# Lamps.net
KiCad netlist of a schematic drawn in Altium Designer
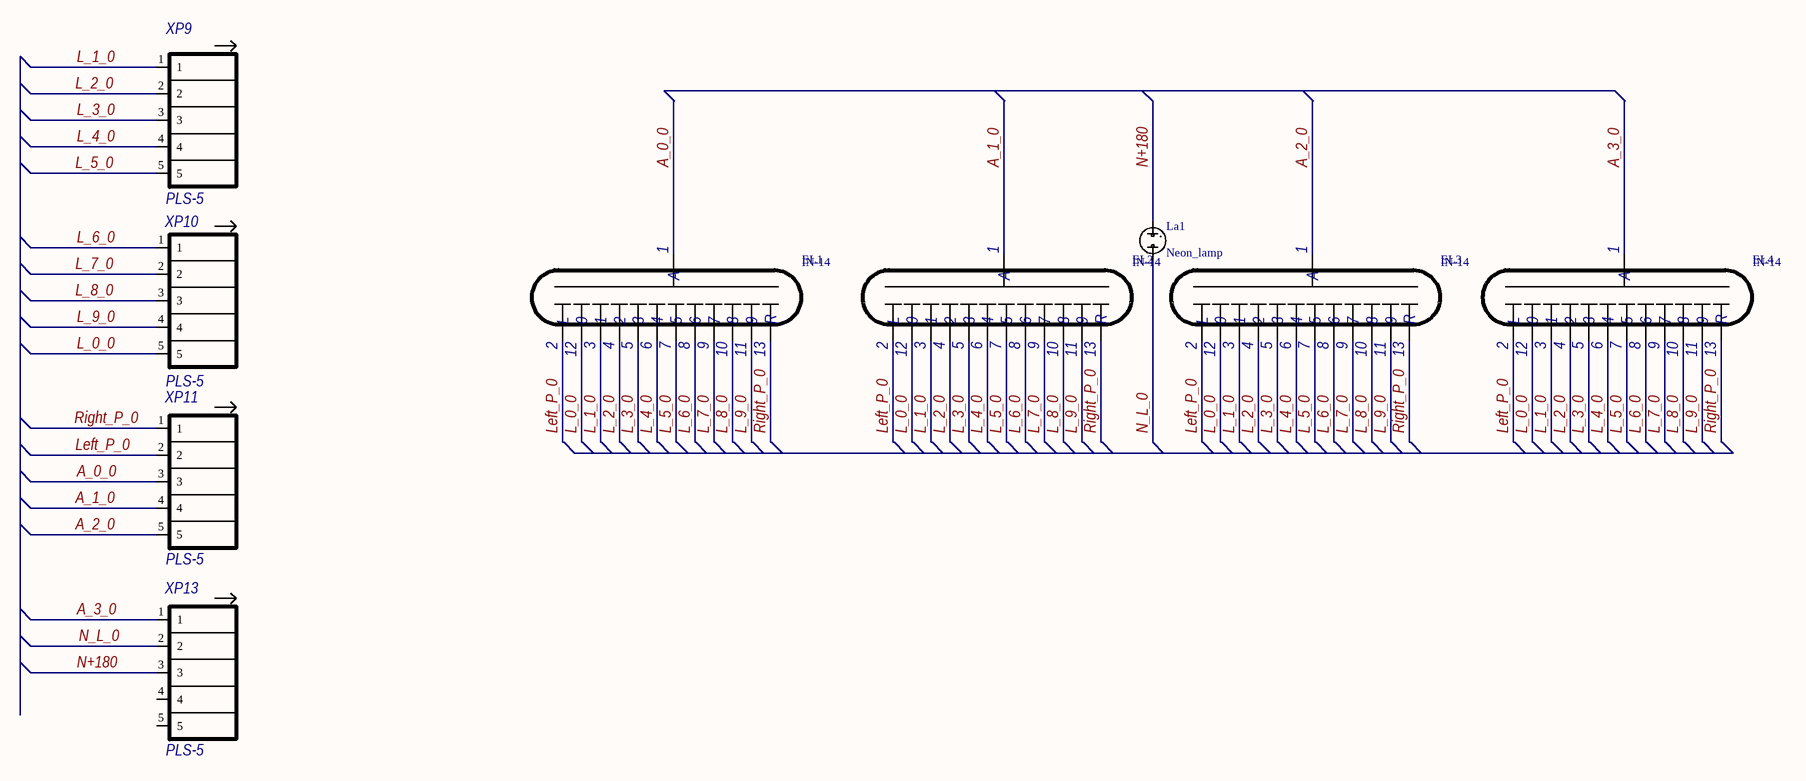
[diagram p0: Lamps.SchDoc]

(export (version "E")
  (design (tool "Eeschema 10.0.6"))
  (components
    (comp (ref "EL1") (value "IN-14") (footprint "IN-14") (libsource (lib "sobol_lib") (part "IN-14")))
    (comp (ref "EL2") (value "IN-14") (footprint "IN-14") (libsource (lib "sobol_lib") (part "IN-14")))
    (comp (ref "EL3") (value "IN-14") (footprint "IN-14") (libsource (lib "sobol_lib") (part "IN-14")))
    (comp (ref "EL4") (value "IN-14") (footprint "IN-14") (libsource (lib "sobol_lib") (part "IN-14")))
    (comp (ref "La1")
      (value "Neon_lamp")
      (footprint "Neon_lamp")
      (fields (field (name "MP") "1N4148") (field (name "MF") "Nexperia USA Inc."))
      (libsource (lib "sobol_lib") (part "Neon_lamp"))
    )
    (comp (ref "XP9") (value "PLS-5") (footprint "PLS-5") (libsource (lib "sobol_lib") (part "PLS-5")))
    (comp (ref "XP10") (value "PLS-5") (footprint "PLS-5") (libsource (lib "sobol_lib") (part "PLS-5")))
    (comp (ref "XP11") (value "PLS-5") (footprint "PLS-5") (libsource (lib "sobol_lib") (part "PLS-5")))
    (comp (ref "XP13") (value "PLS-5") (footprint "PLS-5") (libsource (lib "sobol_lib") (part "PLS-5")))
  )
  (nets
    (net (code "1") (name "/A_0_0") (class "Default")
      (node (ref "EL1") (pin "1") (pinfunction "A_1") (pintype "passive"))
      (node (ref "XP11") (pin "3") (pinfunction "3_3") (pintype "passive"))
    )
    (net (code "2") (name "/A_1_0") (class "Default")
      (node (ref "EL2") (pin "1") (pinfunction "A_1") (pintype "passive"))
      (node (ref "XP11") (pin "4") (pinfunction "4_4") (pintype "passive"))
    )
    (net (code "3") (name "/A_2_0") (class "Default")
      (node (ref "EL3") (pin "1") (pinfunction "A_1") (pintype "passive"))
      (node (ref "XP11") (pin "5") (pinfunction "5_5") (pintype "passive"))
    )
    (net (code "4") (name "/A_3_0") (class "Default")
      (node (ref "EL4") (pin "1") (pinfunction "A_1") (pintype "passive"))
      (node (ref "XP13") (pin "1") (pinfunction "1_1") (pintype "passive"))
    )
    (net (code "5") (name "/L_0_0") (class "Default")
      (node (ref "EL1") (pin "12") (pinfunction "0_12") (pintype "passive"))
      (node (ref "EL2") (pin "12") (pinfunction "0_12") (pintype "passive"))
      (node (ref "EL3") (pin "12") (pinfunction "0_12") (pintype "passive"))
      (node (ref "EL4") (pin "12") (pinfunction "0_12") (pintype "passive"))
      (node (ref "XP10") (pin "5") (pinfunction "5_5") (pintype "passive"))
    )
    (net (code "6") (name "/L_1_0") (class "Default")
      (node (ref "EL1") (pin "3") (pinfunction "1_3") (pintype "passive"))
      (node (ref "EL2") (pin "3") (pinfunction "1_3") (pintype "passive"))
      (node (ref "EL3") (pin "3") (pinfunction "1_3") (pintype "passive"))
      (node (ref "EL4") (pin "3") (pinfunction "1_3") (pintype "passive"))
      (node (ref "XP9") (pin "1") (pinfunction "1_1") (pintype "passive"))
    )
    (net (code "7") (name "/L_2_0") (class "Default")
      (node (ref "EL1") (pin "4") (pinfunction "2_4") (pintype "passive"))
      (node (ref "EL2") (pin "4") (pinfunction "2_4") (pintype "passive"))
      (node (ref "EL3") (pin "4") (pinfunction "2_4") (pintype "passive"))
      (node (ref "EL4") (pin "4") (pinfunction "2_4") (pintype "passive"))
      (node (ref "XP9") (pin "2") (pinfunction "2_2") (pintype "passive"))
    )
    (net (code "8") (name "/L_3_0") (class "Default")
      (node (ref "EL1") (pin "5") (pinfunction "3_5") (pintype "passive"))
      (node (ref "EL2") (pin "5") (pinfunction "3_5") (pintype "passive"))
      (node (ref "EL3") (pin "5") (pinfunction "3_5") (pintype "passive"))
      (node (ref "EL4") (pin "5") (pinfunction "3_5") (pintype "passive"))
      (node (ref "XP9") (pin "3") (pinfunction "3_3") (pintype "passive"))
    )
    (net (code "9") (name "/L_4_0") (class "Default")
      (node (ref "EL1") (pin "6") (pinfunction "4_6") (pintype "passive"))
      (node (ref "EL2") (pin "6") (pinfunction "4_6") (pintype "passive"))
      (node (ref "EL3") (pin "6") (pinfunction "4_6") (pintype "passive"))
      (node (ref "EL4") (pin "6") (pinfunction "4_6") (pintype "passive"))
      (node (ref "XP9") (pin "4") (pinfunction "4_4") (pintype "passive"))
    )
    (net (code "10") (name "/L_5_0") (class "Default")
      (node (ref "EL1") (pin "7") (pinfunction "5_7") (pintype "passive"))
      (node (ref "EL2") (pin "7") (pinfunction "5_7") (pintype "passive"))
      (node (ref "EL3") (pin "7") (pinfunction "5_7") (pintype "passive"))
      (node (ref "EL4") (pin "7") (pinfunction "5_7") (pintype "passive"))
      (node (ref "XP9") (pin "5") (pinfunction "5_5") (pintype "passive"))
    )
    (net (code "11") (name "/L_6_0") (class "Default")
      (node (ref "EL1") (pin "8") (pinfunction "6_8") (pintype "passive"))
      (node (ref "EL2") (pin "8") (pinfunction "6_8") (pintype "passive"))
      (node (ref "EL3") (pin "8") (pinfunction "6_8") (pintype "passive"))
      (node (ref "EL4") (pin "8") (pinfunction "6_8") (pintype "passive"))
      (node (ref "XP10") (pin "1") (pinfunction "1_1") (pintype "passive"))
    )
    (net (code "12") (name "/L_7_0") (class "Default")
      (node (ref "EL1") (pin "9") (pinfunction "7_9") (pintype "passive"))
      (node (ref "EL2") (pin "9") (pinfunction "7_9") (pintype "passive"))
      (node (ref "EL3") (pin "9") (pinfunction "7_9") (pintype "passive"))
      (node (ref "EL4") (pin "9") (pinfunction "7_9") (pintype "passive"))
      (node (ref "XP10") (pin "2") (pinfunction "2_2") (pintype "passive"))
    )
    (net (code "13") (name "/L_8_0") (class "Default")
      (node (ref "EL1") (pin "10") (pinfunction "8_10") (pintype "passive"))
      (node (ref "EL2") (pin "10") (pinfunction "8_10") (pintype "passive"))
      (node (ref "EL3") (pin "10") (pinfunction "8_10") (pintype "passive"))
      (node (ref "EL4") (pin "10") (pinfunction "8_10") (pintype "passive"))
      (node (ref "XP10") (pin "3") (pinfunction "3_3") (pintype "passive"))
    )
    (net (code "14") (name "/L_9_0") (class "Default")
      (node (ref "EL1") (pin "11") (pinfunction "9_11") (pintype "passive"))
      (node (ref "EL2") (pin "11") (pinfunction "9_11") (pintype "passive"))
      (node (ref "EL3") (pin "11") (pinfunction "9_11") (pintype "passive"))
      (node (ref "EL4") (pin "11") (pinfunction "9_11") (pintype "passive"))
      (node (ref "XP10") (pin "4") (pinfunction "4_4") (pintype "passive"))
    )
    (net (code "15") (name "/Left_P_0") (class "Default")
      (node (ref "EL1") (pin "2") (pinfunction "L_2") (pintype "passive"))
      (node (ref "EL2") (pin "2") (pinfunction "L_2") (pintype "passive"))
      (node (ref "EL3") (pin "2") (pinfunction "L_2") (pintype "passive"))
      (node (ref "EL4") (pin "2") (pinfunction "L_2") (pintype "passive"))
      (node (ref "XP11") (pin "2") (pinfunction "2_2") (pintype "passive"))
    )
    (net (code "16") (name "/N+180") (class "Default")
      (node (ref "La1") (pin "1") (pinfunction "A_1") (pintype "passive"))
      (node (ref "XP13") (pin "3") (pinfunction "3_3") (pintype "passive"))
    )
    (net (code "17") (name "/N_L_0") (class "Default")
      (node (ref "La1") (pin "2") (pinfunction "C_2") (pintype "passive"))
      (node (ref "XP13") (pin "2") (pinfunction "2_2") (pintype "passive"))
    )
    (net (code "18") (name "/Right_P_0") (class "Default")
      (node (ref "EL1") (pin "13") (pinfunction "R_13") (pintype "passive"))
      (node (ref "EL2") (pin "13") (pinfunction "R_13") (pintype "passive"))
      (node (ref "EL3") (pin "13") (pinfunction "R_13") (pintype "passive"))
      (node (ref "EL4") (pin "13") (pinfunction "R_13") (pintype "passive"))
      (node (ref "XP11") (pin "1") (pinfunction "1_1") (pintype "passive"))
    )
    (net (code "19") (name "unconnected-(XP13-Pad4)") (class "Default")
      (node (ref "XP13") (pin "4") (pinfunction "4_4") (pintype "passive"))
    )
    (net (code "20") (name "unconnected-(XP13-Pad5)") (class "Default")
      (node (ref "XP13") (pin "5") (pinfunction "5_5") (pintype "passive"))
    )
  )
)
